# cat-badge.net
KiCad netlist of a schematic drawn in Altium Designer
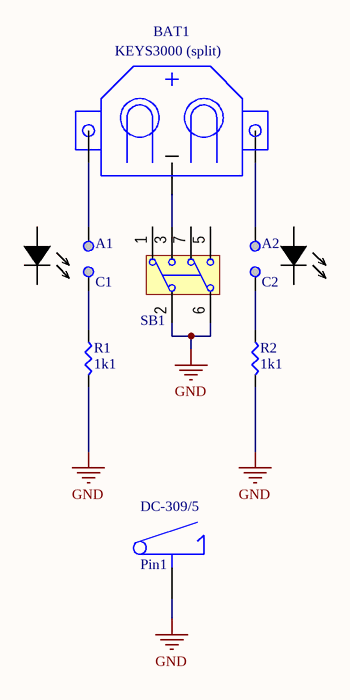
[diagram p0: cat-badge.SchDoc]

(export (version "E")
  (design (tool "Eeschema 10.0.6"))
  (components
    (comp (ref "A1")
      (value "Test Point")
      (footprint "TP_1.2MM")
      (fields (field (name "PART NUMBER") "TP/R1.2"))
      (libsource (lib "Lib_Kam") (part "Test Point"))
    )
    (comp (ref "A2")
      (value "Test Point")
      (footprint "TP_1.2MM")
      (fields (field (name "PART NUMBER") "TP/R1.2"))
      (libsource (lib "Lib_Kam") (part "Test Point"))
    )
    (comp (ref "BAT1")
      (value "KEYS3000 (split)")
      (footprint "KEYS3000_split")
      (description "Coin Cell Battery Holders SMT HOLDER FOR CR1220")
      (fields (field (name "MANUFACTURER") "KEYSTONE"))
      (libsource (lib "Lib_Kam") (part "Coin_battery"))
    )
    (comp (ref "C1")
      (value "Test Point")
      (footprint "TP_1.2MM")
      (fields (field (name "PART NUMBER") "TP/R1.2"))
      (libsource (lib "Lib_Kam") (part "Test Point"))
    )
    (comp (ref "C2")
      (value "Test Point")
      (footprint "TP_1.2MM")
      (fields (field (name "PART NUMBER") "TP/R1.2"))
      (libsource (lib "Lib_Kam") (part "Test Point"))
    )
    (comp (ref "Pin1")
      (value "DC-309/5")
      (footprint "DC-309/5")
      (description "Bar pin 20mm")
      (fields (field (name "MANUFACTURER") "none"))
      (libsource (lib "Lib_Kam") (part "Bar-pin"))
    )
    (comp (ref "R1")
      (value "1k1")
      (footprint "RES0603")
      (description "Tolerance ±1%\nPower (Watts) 0.1W, 1/10W\nTemperature Coefficient ±100ppm/°C")
      (fields (field (name "PART NUMBER") "ERJ-3EKF1101V") (field (name "TOLERANCE") "1%"))
      (libsource (lib "Lib_Kam") (part "Resistor"))
    )
    (comp (ref "R2")
      (value "1k1")
      (footprint "RES0603")
      (description "Tolerance ±1%\nPower (Watts) 0.1W, 1/10W\nTemperature Coefficient ±100ppm/°C")
      (fields (field (name "PART NUMBER") "ERJ-3EKF1101V") (field (name "TOLERANCE") "1%"))
      (libsource (lib "Lib_Kam") (part "Resistor"))
    )
    (comp (ref "SB1")
      (value "JS202011JCQN")
      (footprint "JS202011JCQN")
      (description "Slide Switches DPDT .3A")
      (fields (field (name "MANUFACTURER") "C&K Switches"))
      (libsource (lib "Lib_Kam") (part "DPDT_C_K_Switches"))
    )
  )
  (nets
    (net (code "1") (name "GND") (class "Default")
      (node (ref "Pin1") (pin "1") (pinfunction "1_1") (pintype "passive"))
      (node (ref "R1") (pin "1") (pintype "passive"))
      (node (ref "R2") (pin "1") (pintype "passive"))
      (node (ref "SB1") (pin "2") (pintype "passive"))
      (node (ref "SB1") (pin "6") (pintype "passive"))
    )
    (net (code "2") (name "Net-(A1-Pad1)") (class "Default")
      (node (ref "A1") (pin "1") (pinfunction "1_1") (pintype "passive"))
      (node (ref "BAT1") (pin "3") (pinfunction "1_3") (pintype "passive"))
    )
    (net (code "3") (name "Net-(A2-Pad1)") (class "Default")
      (node (ref "A2") (pin "1") (pinfunction "1_1") (pintype "passive"))
      (node (ref "BAT1") (pin "1") (pinfunction "1_1") (pintype "passive"))
    )
    (net (code "4") (name "Net-(BAT1-Pad2)") (class "Default")
      (node (ref "BAT1") (pin "2") (pinfunction "2_2") (pintype "passive"))
      (node (ref "SB1") (pin "3") (pintype "passive"))
    )
    (net (code "5") (name "Net-(C1-Pad1)") (class "Default")
      (node (ref "C1") (pin "1") (pinfunction "1_1") (pintype "passive"))
      (node (ref "R1") (pin "2") (pintype "passive"))
    )
    (net (code "6") (name "Net-(C2-Pad1)") (class "Default")
      (node (ref "C2") (pin "1") (pinfunction "1_1") (pintype "passive"))
      (node (ref "R2") (pin "2") (pintype "passive"))
    )
    (net (code "7") (name "unconnected-(SB1-Pad1)") (class "Default")
      (node (ref "SB1") (pin "1") (pintype "passive"))
    )
    (net (code "8") (name "unconnected-(SB1-Pad5)") (class "Default")
      (node (ref "SB1") (pin "5") (pintype "passive"))
    )
    (net (code "9") (name "unconnected-(SB1-Pad7)") (class "Default")
      (node (ref "SB1") (pin "7") (pintype "passive"))
    )
  )
)
